# CY8C4125AZI-S433.net
KiCad netlist of a schematic drawn in Altium Designer
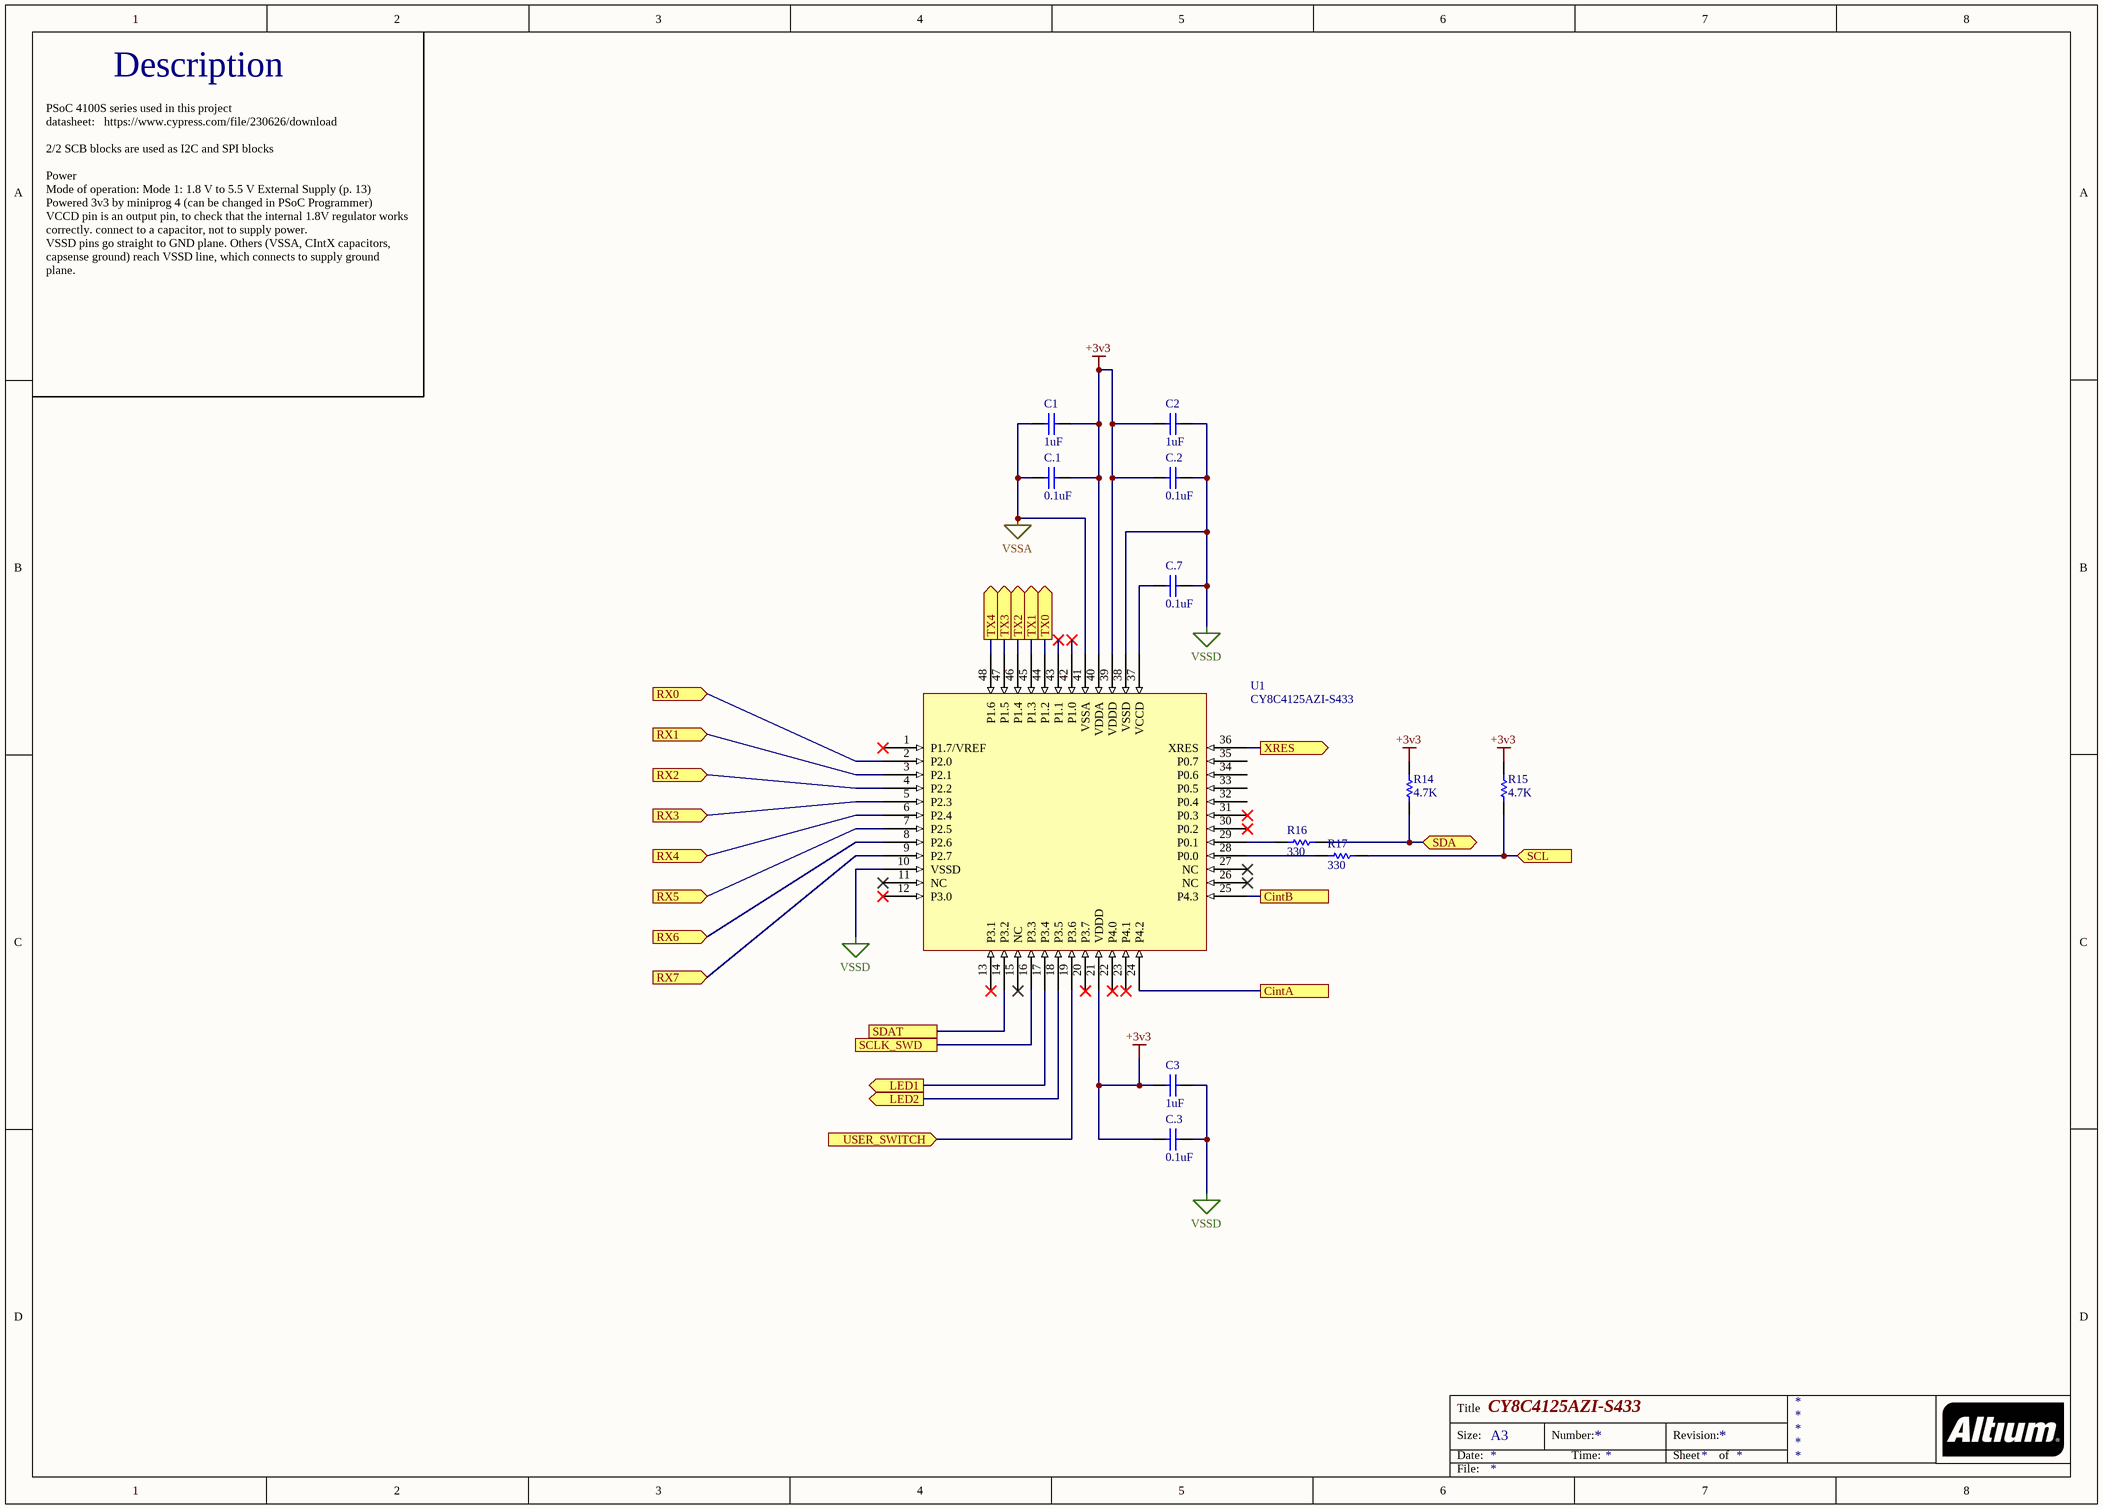
[diagram p0: CY8C4125AZI-S433.SchDoc]

(export (version "E")
  (design (tool "Eeschema 10.0.6"))
  (components
    (comp (ref "C.1")
      (value "0.1uF")
      (footprint "CAPC0603(1608)100_N")
      (description "CAP 0.1 uF 50V ±20% 0603 (1608 Metric) Thickness 1mm SMD")
      (fields (field (name "TOLERANCE") "Â±20%"))
      (libsource (lib "Altium Content Vault") (part "CAP"))
    )
    (comp (ref "C.2")
      (value "0.1uF")
      (footprint "CAPC0603(1608)100_N")
      (description "CAP 0.1 uF 50V ±20% 0603 (1608 Metric) Thickness 1mm SMD")
      (fields (field (name "TOLERANCE") "Â±20%"))
      (libsource (lib "Altium Content Vault") (part "CAP"))
    )
    (comp (ref "C.3")
      (value "0.1uF")
      (footprint "CAPC0603(1608)100_N")
      (description "CAP 0.1 uF 50V ±20% 0603 (1608 Metric) Thickness 1mm SMD")
      (fields (field (name "TOLERANCE") "Â±20%"))
      (libsource (lib "Altium Content Vault") (part "CAP"))
    )
    (comp (ref "C.7")
      (value "0.1uF")
      (footprint "CAPC0603(1608)100_N")
      (description "CAP 0.1 uF 50V ±20% 0603 (1608 Metric) Thickness 1mm SMD")
      (fields (field (name "TOLERANCE") "Â±20%"))
      (libsource (lib "Altium Content Vault") (part "CAP"))
    )
    (comp (ref "C1")
      (value "1uF")
      (footprint "CAPC0603(1608)100_N")
      (description "CAP 1uF 50V ±20% 0603 (1608 Metric) Thickness 1mm SMD")
      (fields (field (name "TOLERANCE") "Â±20%"))
      (libsource (lib "Altium Content Vault") (part "CAP"))
    )
    (comp (ref "C2")
      (value "1uF")
      (footprint "CAPC0603(1608)100_N")
      (description "CAP 1uF 50V ±20% 0603 (1608 Metric) Thickness 1mm SMD")
      (fields (field (name "TOLERANCE") "Â±20%"))
      (libsource (lib "Altium Content Vault") (part "CAP"))
    )
    (comp (ref "C3")
      (value "1uF")
      (footprint "CAPC0603(1608)100_N")
      (description "CAP 1uF 50V ±20% 0603 (1608 Metric) Thickness 1mm SMD")
      (fields (field (name "TOLERANCE") "Â±20%"))
      (libsource (lib "Altium Content Vault") (part "CAP"))
    )
    (comp (ref "R14")
      (value "4.7K")
      (footprint "RESC1608X55X25ML10T15")
      (fields (field (name "TOLERANCE") "5%") (field (name "MANUFACTURER") "Yageo"))
      (libsource (lib "Altium Content Vault") (part "RES-2"))
    )
    (comp (ref "R15")
      (value "4.7K")
      (footprint "RESC1608X55X25ML10T15")
      (fields (field (name "TOLERANCE") "5%") (field (name "MANUFACTURER") "Yageo"))
      (libsource (lib "Altium Content Vault") (part "RES-2"))
    )
    (comp (ref "R16")
      (value "330")
      (footprint "RESC0603(1608)_L")
      (description "330R 0.1W 5% 0603 (1608 Metric)  SMD")
      (fields (field (name "TOLERANCE") "5 %") (field (name "POWER") "0.1 W"))
      (libsource (lib "Altium Content Vault") (part "RES"))
    )
    (comp (ref "R17")
      (value "330")
      (footprint "RESC0603(1608)_L")
      (description "330R 0.1W 5% 0603 (1608 Metric)  SMD")
      (fields (field (name "TOLERANCE") "5 %") (field (name "POWER") "0.1 W"))
      (libsource (lib "Altium Content Vault") (part "RES"))
    )
    (comp (ref "U1")
      (value "CY8C4125AZI-S433")
      (footprint "CY8C4125AZI-S433")
      (libsource (lib "PSOC") (part "CY8C4125AZI-S433"))
    )
  )
  (nets
    (net (code "1") (name "+3v3") (class "Default")
      (node (ref "C.1") (pin "2") (pinfunction "2_2") (pintype "passive"))
      (node (ref "C.2") (pin "1") (pinfunction "1_1") (pintype "passive"))
      (node (ref "C.3") (pin "1") (pinfunction "1_1") (pintype "passive"))
      (node (ref "C1") (pin "2") (pinfunction "2_2") (pintype "passive"))
      (node (ref "C2") (pin "1") (pinfunction "1_1") (pintype "passive"))
      (node (ref "C3") (pin "1") (pinfunction "1_1") (pintype "passive"))
      (node (ref "R14") (pin "2") (pinfunction "2_2") (pintype "passive"))
      (node (ref "R15") (pin "2") (pinfunction "2_2") (pintype "passive"))
      (node (ref "U1") (pin "21") (pinfunction "VDDD_21") (pintype "input"))
      (node (ref "U1") (pin "39") (pinfunction "VDDD_39") (pintype "input"))
      (node (ref "U1") (pin "40") (pinfunction "VDDA_40") (pintype "input"))
    )
    (net (code "2") (name "/CintA") (class "Default")
      (node (ref "U1") (pin "24") (pinfunction "P4.2_24") (pintype "input"))
    )
    (net (code "3") (name "/CintB") (class "Default")
      (node (ref "U1") (pin "25") (pinfunction "P4.3_25") (pintype "input"))
    )
    (net (code "4") (name "/LED1") (class "Default")
      (node (ref "U1") (pin "17") (pinfunction "P3.4_17") (pintype "input"))
    )
    (net (code "5") (name "/LED2") (class "Default")
      (node (ref "U1") (pin "18") (pinfunction "P3.5_18") (pintype "input"))
    )
    (net (code "6") (name "/RX0") (class "Default")
      (node (ref "U1") (pin "2") (pinfunction "P2.0_2") (pintype "input"))
    )
    (net (code "7") (name "/RX1") (class "Default")
      (node (ref "U1") (pin "3") (pinfunction "P2.1_3") (pintype "input"))
    )
    (net (code "8") (name "/RX2") (class "Default")
      (node (ref "U1") (pin "4") (pinfunction "P2.2_4") (pintype "input"))
    )
    (net (code "9") (name "/RX3") (class "Default")
      (node (ref "U1") (pin "5") (pinfunction "P2.3_5") (pintype "input"))
    )
    (net (code "10") (name "/RX4") (class "Default")
      (node (ref "U1") (pin "6") (pinfunction "P2.4_6") (pintype "input"))
    )
    (net (code "11") (name "/RX5") (class "Default")
      (node (ref "U1") (pin "7") (pinfunction "P2.5_7") (pintype "input"))
    )
    (net (code "12") (name "/RX6") (class "Default")
      (node (ref "U1") (pin "8") (pinfunction "P2.6_8") (pintype "input"))
    )
    (net (code "13") (name "/RX7") (class "Default")
      (node (ref "U1") (pin "9") (pinfunction "P2.7_9") (pintype "input"))
    )
    (net (code "14") (name "/SCL") (class "Default")
      (node (ref "R15") (pin "1") (pinfunction "1_1") (pintype "passive"))
      (node (ref "R17") (pin "2") (pinfunction "2_2") (pintype "passive"))
    )
    (net (code "15") (name "/SCLK_SWD") (class "Default")
      (node (ref "U1") (pin "16") (pinfunction "P3.3_16") (pintype "input"))
    )
    (net (code "16") (name "/SDA") (class "Default")
      (node (ref "R14") (pin "1") (pinfunction "1_1") (pintype "passive"))
      (node (ref "R16") (pin "2") (pinfunction "2_2") (pintype "passive"))
    )
    (net (code "17") (name "/SDAT") (class "Default")
      (node (ref "U1") (pin "14") (pinfunction "P3.2_14") (pintype "input"))
    )
    (net (code "18") (name "/TX0") (class "Default")
      (node (ref "U1") (pin "44") (pinfunction "P1.2_44") (pintype "input"))
    )
    (net (code "19") (name "/TX1") (class "Default")
      (node (ref "U1") (pin "45") (pinfunction "P1.3_45") (pintype "input"))
    )
    (net (code "20") (name "/TX2") (class "Default")
      (node (ref "U1") (pin "46") (pinfunction "P1.4_46") (pintype "input"))
    )
    (net (code "21") (name "/TX3") (class "Default")
      (node (ref "U1") (pin "47") (pinfunction "P1.5_47") (pintype "input"))
    )
    (net (code "22") (name "/TX4") (class "Default")
      (node (ref "U1") (pin "48") (pinfunction "P1.6_48") (pintype "input"))
    )
    (net (code "23") (name "/USER_SWITCH") (class "Default")
      (node (ref "U1") (pin "19") (pinfunction "P3.6_19") (pintype "input"))
    )
    (net (code "24") (name "/XRES") (class "Default")
      (node (ref "U1") (pin "36") (pinfunction "XRES_36") (pintype "input"))
    )
    (net (code "25") (name "Net-(U1-P0.0)") (class "Default")
      (node (ref "R17") (pin "1") (pinfunction "1_1") (pintype "passive"))
      (node (ref "U1") (pin "28") (pinfunction "P0.0_28") (pintype "input"))
    )
    (net (code "26") (name "Net-(U1-P0.1)") (class "Default")
      (node (ref "R16") (pin "1") (pinfunction "1_1") (pintype "passive"))
      (node (ref "U1") (pin "29") (pinfunction "P0.1_29") (pintype "input"))
    )
    (net (code "27") (name "Net-(U1-VCCD)") (class "Default")
      (node (ref "C.7") (pin "1") (pinfunction "1_1") (pintype "passive"))
      (node (ref "U1") (pin "37") (pinfunction "VCCD_37") (pintype "input"))
    )
    (net (code "28") (name "VSSA") (class "Default")
      (node (ref "C.1") (pin "1") (pinfunction "1_1") (pintype "passive"))
      (node (ref "C1") (pin "1") (pinfunction "1_1") (pintype "passive"))
      (node (ref "U1") (pin "41") (pinfunction "VSSA_41") (pintype "input"))
    )
    (net (code "29") (name "VSSD") (class "Default")
      (node (ref "C.2") (pin "2") (pinfunction "2_2") (pintype "passive"))
      (node (ref "C.3") (pin "2") (pinfunction "2_2") (pintype "passive"))
      (node (ref "C.7") (pin "2") (pinfunction "2_2") (pintype "passive"))
      (node (ref "C2") (pin "2") (pinfunction "2_2") (pintype "passive"))
      (node (ref "C3") (pin "2") (pinfunction "2_2") (pintype "passive"))
      (node (ref "U1") (pin "10") (pinfunction "VSSD_10") (pintype "input"))
      (node (ref "U1") (pin "38") (pinfunction "VSSD_38") (pintype "input"))
    )
    (net (code "30") (name "unconnected-(U1-NC-Pad11)") (class "Default")
      (node (ref "U1") (pin "11") (pinfunction "NC_11") (pintype "input+no_connect"))
    )
    (net (code "31") (name "unconnected-(U1-NC-Pad15)") (class "Default")
      (node (ref "U1") (pin "15") (pinfunction "NC_15") (pintype "input+no_connect"))
    )
    (net (code "32") (name "unconnected-(U1-NC-Pad26)") (class "Default")
      (node (ref "U1") (pin "26") (pinfunction "NC_26") (pintype "input+no_connect"))
    )
    (net (code "33") (name "unconnected-(U1-NC-Pad27)") (class "Default")
      (node (ref "U1") (pin "27") (pinfunction "NC_27") (pintype "input+no_connect"))
    )
    (net (code "34") (name "unconnected-(U1-P0.2-Pad30)") (class "Default")
      (node (ref "U1") (pin "30") (pinfunction "P0.2_30") (pintype "input+no_connect"))
    )
    (net (code "35") (name "unconnected-(U1-P0.3-Pad31)") (class "Default")
      (node (ref "U1") (pin "31") (pinfunction "P0.3_31") (pintype "input+no_connect"))
    )
    (net (code "36") (name "unconnected-(U1-P0.4-Pad32)") (class "Default")
      (node (ref "U1") (pin "32") (pinfunction "P0.4_32") (pintype "input"))
    )
    (net (code "37") (name "unconnected-(U1-P0.5-Pad33)") (class "Default")
      (node (ref "U1") (pin "33") (pinfunction "P0.5_33") (pintype "input"))
    )
    (net (code "38") (name "unconnected-(U1-P0.6-Pad34)") (class "Default")
      (node (ref "U1") (pin "34") (pinfunction "P0.6_34") (pintype "input"))
    )
    (net (code "39") (name "unconnected-(U1-P0.7-Pad35)") (class "Default")
      (node (ref "U1") (pin "35") (pinfunction "P0.7_35") (pintype "input"))
    )
    (net (code "40") (name "unconnected-(U1-P1.0-Pad42)") (class "Default")
      (node (ref "U1") (pin "42") (pinfunction "P1.0_42") (pintype "input+no_connect"))
    )
    (net (code "41") (name "unconnected-(U1-P1.1-Pad43)") (class "Default")
      (node (ref "U1") (pin "43") (pinfunction "P1.1_43") (pintype "input+no_connect"))
    )
    (net (code "42") (name "unconnected-(U1-P1.7{slash}VREF-Pad1)") (class "Default")
      (node (ref "U1") (pin "1") (pinfunction "P1.7/VREF_1") (pintype "input+no_connect"))
    )
    (net (code "43") (name "unconnected-(U1-P3.0-Pad12)") (class "Default")
      (node (ref "U1") (pin "12") (pinfunction "P3.0_12") (pintype "input+no_connect"))
    )
    (net (code "44") (name "unconnected-(U1-P3.1-Pad13)") (class "Default")
      (node (ref "U1") (pin "13") (pinfunction "P3.1_13") (pintype "input+no_connect"))
    )
    (net (code "45") (name "unconnected-(U1-P3.7-Pad20)") (class "Default")
      (node (ref "U1") (pin "20") (pinfunction "P3.7_20") (pintype "input+no_connect"))
    )
    (net (code "46") (name "unconnected-(U1-P4.0-Pad22)") (class "Default")
      (node (ref "U1") (pin "22") (pinfunction "P4.0_22") (pintype "input+no_connect"))
    )
    (net (code "47") (name "unconnected-(U1-P4.1-Pad23)") (class "Default")
      (node (ref "U1") (pin "23") (pinfunction "P4.1_23") (pintype "input+no_connect"))
    )
  )
)
